# CH32M030C9U_PD-EVT.net
KiCad netlist of a schematic drawn in Altium Designer
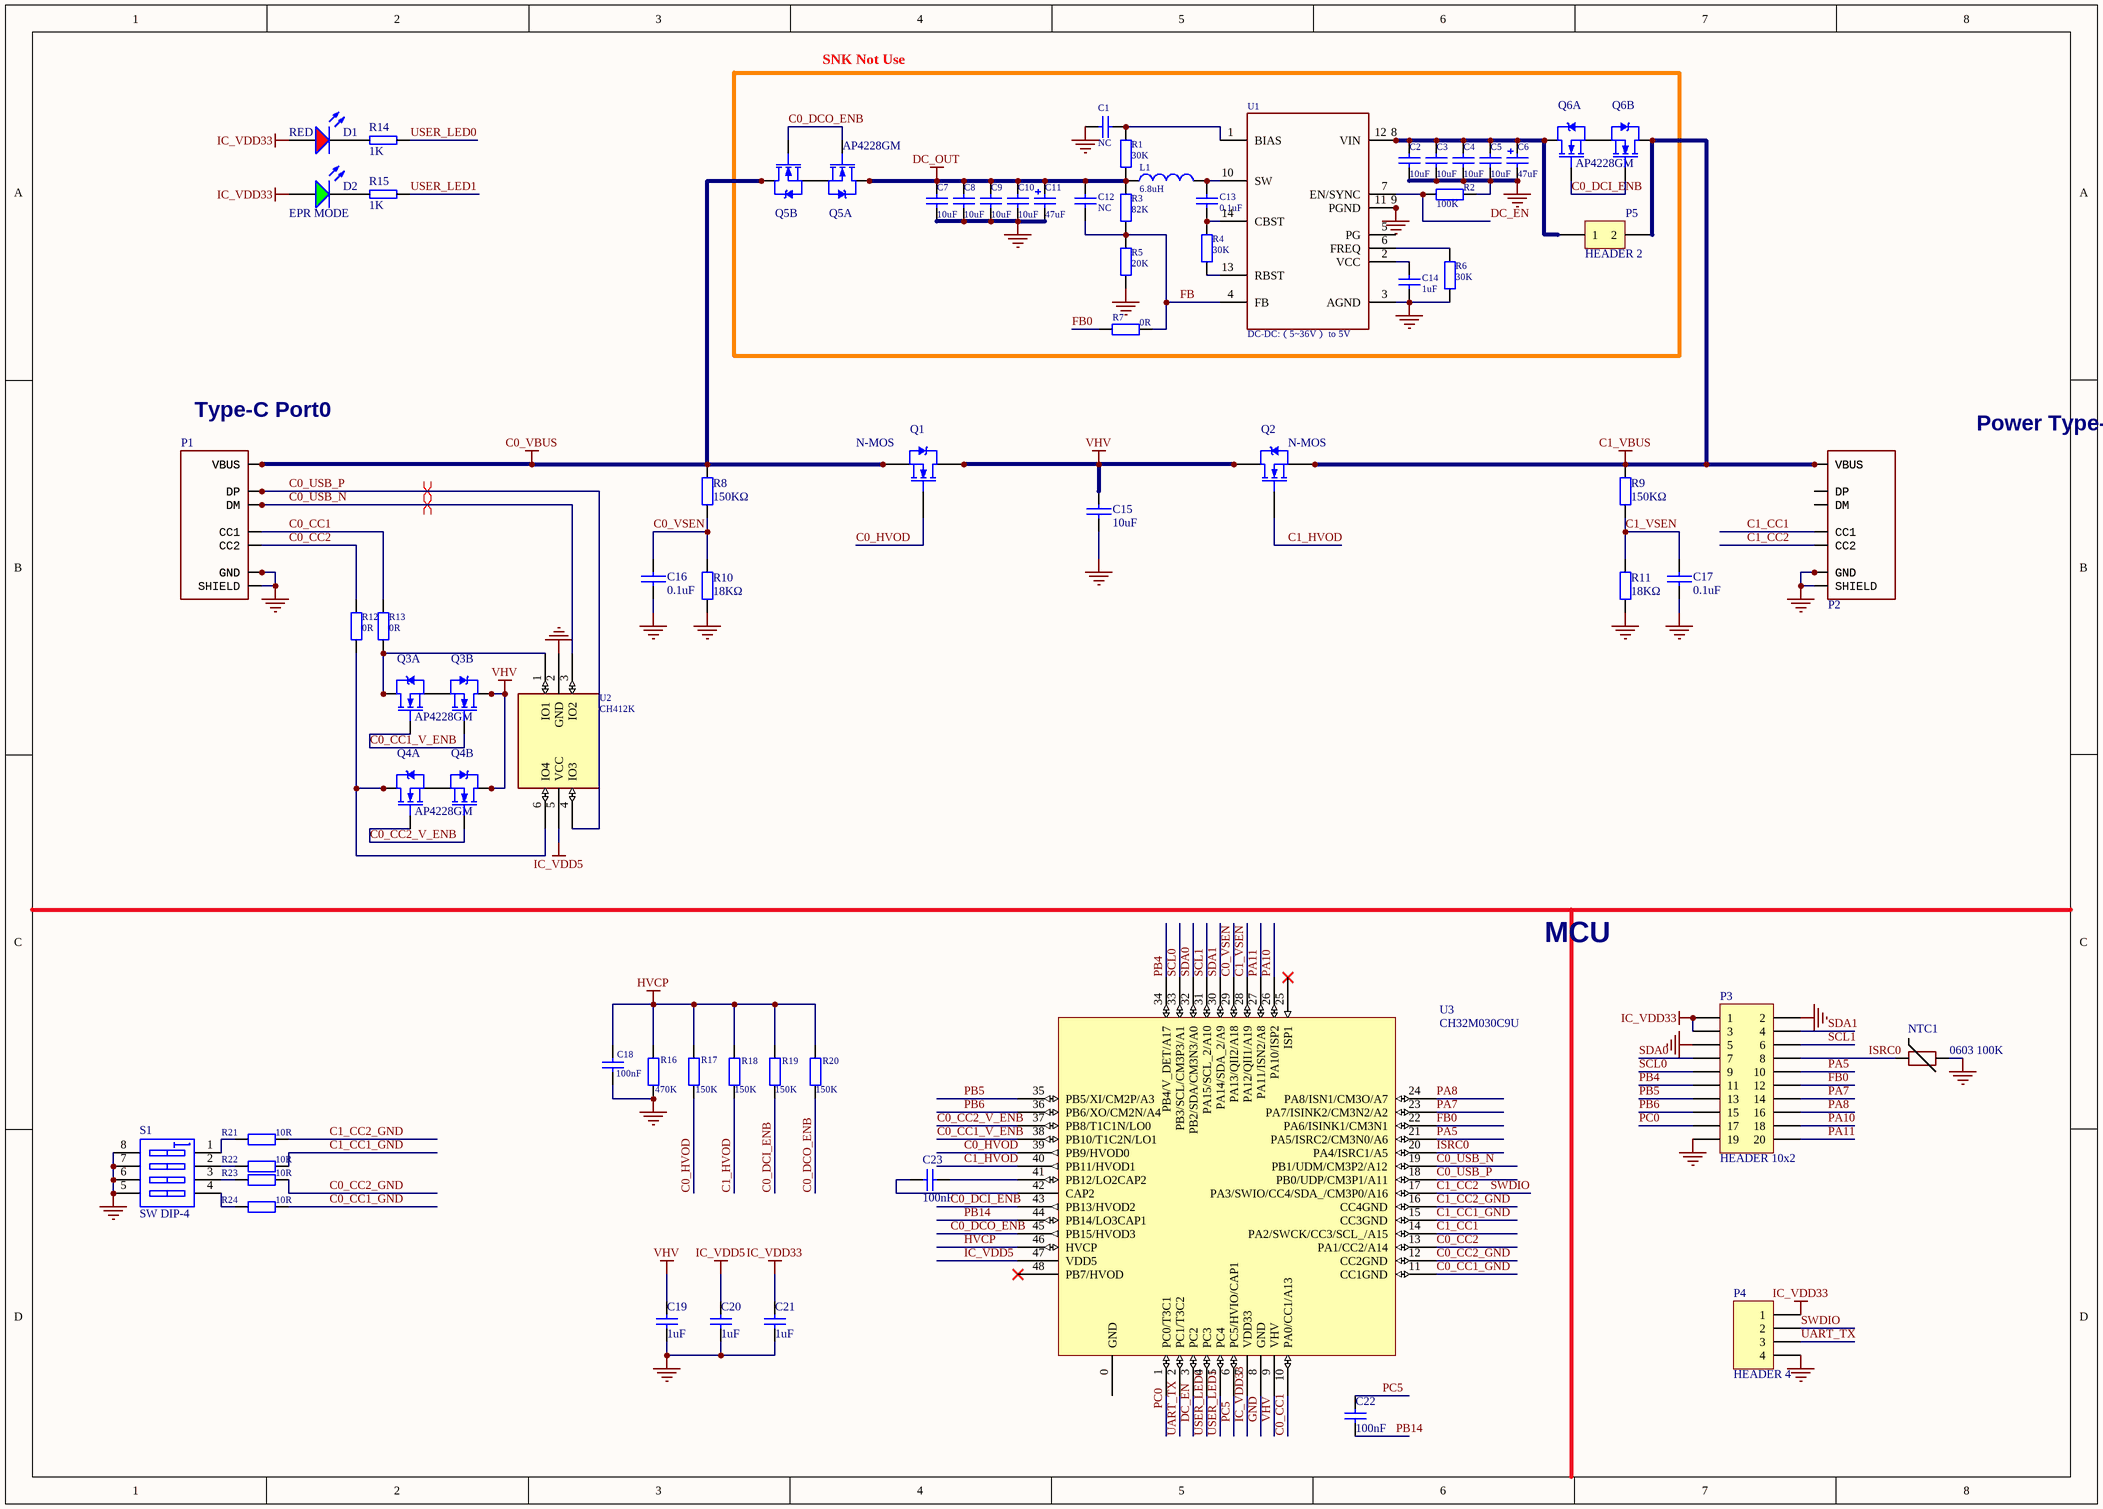
[diagram p0: CH32M030C9U_PD-EVT.SchDoc]

(export (version "E")
  (design (tool "Eeschema 10.0.6"))
  (components
    (comp (ref "C1")
      (value "NC")
      (footprint "0402_C")
      (description "贴片电容")
      (libsource (lib "Miscellaneous Devices LC") (part "0603 100nF (104) 10% 50V"))
    )
    (comp (ref "C2")
      (value "10uF")
      (footprint "0603_C")
      (description "贴片电容")
      (libsource (lib "Miscellaneous Devices LC") (part "0603 100nF (104) 10% 50V"))
    )
    (comp (ref "C3")
      (value "10uF")
      (footprint "0603_C")
      (description "贴片电容")
      (libsource (lib "Miscellaneous Devices LC") (part "0603 100nF (104) 10% 50V"))
    )
    (comp (ref "C4")
      (value "10uF")
      (footprint "0603_C")
      (description "贴片电容")
      (libsource (lib "Miscellaneous Devices LC") (part "0603 100nF (104) 10% 50V"))
    )
    (comp (ref "C5")
      (value "10uF")
      (footprint "0603_C")
      (description "贴片电容")
      (libsource (lib "Miscellaneous Devices LC") (part "0603 100nF (104) 10% 50V"))
    )
    (comp (ref "C6")
      (value "47uF")
      (footprint "1206_C")
      (description "钽电容")
      (libsource (lib "Miscellaneous Devices LC") (part "3216 10uF (106) 10% 16V"))
    )
    (comp (ref "C7")
      (value "10uF")
      (footprint "0603_C")
      (description "贴片电容")
      (libsource (lib "Miscellaneous Devices LC") (part "0603 100nF (104) 10% 50V"))
    )
    (comp (ref "C8")
      (value "10uF")
      (footprint "0603_C")
      (description "贴片电容")
      (libsource (lib "Miscellaneous Devices LC") (part "0603 100nF (104) 10% 50V"))
    )
    (comp (ref "C9")
      (value "10uF")
      (footprint "0603_C")
      (description "贴片电容")
      (libsource (lib "Miscellaneous Devices LC") (part "0603 100nF (104) 10% 50V"))
    )
    (comp (ref "C10")
      (value "10uF")
      (footprint "0603_C")
      (description "贴片电容")
      (libsource (lib "Miscellaneous Devices LC") (part "0603 100nF (104) 10% 50V"))
    )
    (comp (ref "C11")
      (value "47uF")
      (footprint "1206_C")
      (description "钽电容")
      (libsource (lib "Miscellaneous Devices LC") (part "3216 10uF (106) 10% 16V"))
    )
    (comp (ref "C12")
      (value "NC")
      (footprint "0402_C")
      (description "贴片电容")
      (libsource (lib "Miscellaneous Devices LC") (part "0603 100nF (104) 10% 50V"))
    )
    (comp (ref "C13")
      (value "0.1uF")
      (footprint "0402_C")
      (description "贴片电容")
      (libsource (lib "Miscellaneous Devices LC") (part "0603 100nF (104) 10% 50V"))
    )
    (comp (ref "C14")
      (value "1uF")
      (footprint "0402_C")
      (description "贴片电容")
      (libsource (lib "Miscellaneous Devices LC") (part "0603 100nF (104) 10% 50V"))
    )
    (comp (ref "C15")
      (value "10uF")
      (footprint "0603_C")
      (description "Capacitor")
      (libsource (lib "wch_sch_others") (part "CAP"))
    )
    (comp (ref "C16")
      (value "0.1uF")
      (footprint "0402_C")
      (description "Capacitor")
      (libsource (lib "wch_sch_others") (part "CAP"))
    )
    (comp (ref "C17")
      (value "0.1uF")
      (footprint "0402_C")
      (description "Capacitor")
      (libsource (lib "wch_sch_others") (part "CAP"))
    )
    (comp (ref "C18")
      (value "100nF")
      (footprint "0402_C")
      (description "贴片电容")
      (libsource (lib "Miscellaneous Devices LC") (part "0603 1uF (105) 10% 50V"))
    )
    (comp (ref "C19")
      (value "1uF")
      (footprint "0402_C")
      (description "贴片电容")
      (libsource (lib "Miscellaneous Devices LC") (part "0402 1.0uF (105) 10% 25V"))
    )
    (comp (ref "C20")
      (value "1uF")
      (footprint "0402_C")
      (description "贴片电容")
      (libsource (lib "Miscellaneous Devices LC") (part "0402 1.0uF (105) 10% 25V"))
    )
    (comp (ref "C21")
      (value "1uF")
      (footprint "0402_C")
      (description "贴片电容")
      (libsource (lib "Miscellaneous Devices LC") (part "0402 1.0uF (105) 10% 25V"))
    )
    (comp (ref "C22")
      (value "100nF")
      (footprint "0402_C")
      (description "贴片电容")
      (libsource (lib "Miscellaneous Devices LC") (part "0402 1.0uF (105) 10% 25V"))
    )
    (comp (ref "C23")
      (value "100nF")
      (footprint "0402_C")
      (description "贴片电容")
      (libsource (lib "Miscellaneous Devices LC") (part "0402 1.0uF (105) 10% 25V"))
    )
    (comp (ref "D1")
      (value "RED")
      (footprint "0603+")
      (description "发光二极管")
      (libsource (lib "wch_sch_others") (part "LED-RED"))
    )
    (comp (ref "D2")
      (value "EPR MODE")
      (footprint "0603+")
      (description "发光二极管")
      (libsource (lib "wch_sch_others") (part "LED-GREEN"))
    )
    (comp (ref "L1")
      (value "6.8uH")
      (footprint "IND-SMD_L11.5-W10.0")
      (description "C177243")
      (fields (field (name "PUBLISHER") "Altium Limited"))
      (libsource (lib "Miscellaneous Devices") (part "Inductor"))
    )
    (comp (ref "NTC1")
      (value "0603 100K")
      (footprint "0603")
      (libsource (lib "Miscellaneous SCH Lib") (part "NTC"))
    )
    (comp (ref "P1")
      (value "TYPE-C-Receptacle-RefDesign")
      (footprint "TYPE-C-Receptacle-2.0")
      (libsource (lib "") (part "TYPE-C-Receptacle-RefDesign_1"))
    )
    (comp (ref "P2")
      (value "TYPE-C-Receptacle-RefDesign")
      (footprint "TYPE-C-Receptacle-2.0")
      (libsource (lib "Miscellaneous SCH Lib") (part "TYPE-C-Receptacle-RefDesign"))
    )
    (comp (ref "P3")
      (value "HEADER 10x2")
      (footprint "MYPCB:IDC20-2.54MM")
      (description "Header, 10-Pin, Dual row")
      (libsource (lib "wch_sch_others") (part "HEADER 10x2"))
    )
    (comp (ref "P4")
      (value "HEADER 4")
      (footprint "SIP4-2.54mm")
      (description "Header, 4-Pin")
      (libsource (lib "wch_sch_others") (part "HEADER 4"))
    )
    (comp (ref "P5")
      (value "HEADER 2")
      (footprint "MYPCB:SIP2-2.54mm")
      (description "Header, 2-Pin")
      (libsource (lib "wch_sch_others") (part "HEADER 2_1"))
    )
    (comp (ref "Q1")
      (value "N-MOS")
      (footprint "DFN-8_L3.1-W3.0-P0.65-LS3.3-BL")
      (description "N-MOS 8p")
      (libsource (lib "Miscellaneous SCH Lib") (part "N-MOS"))
    )
    (comp (ref "Q2")
      (value "N-MOS")
      (footprint "DFN-8_L3.1-W3.0-P0.65-LS3.3-BL")
      (description "N-MOS 8p")
      (libsource (lib "Miscellaneous SCH Lib") (part "N-MOS"))
    )
    (comp (ref "Q3")
      (value "AP4228GM")
      (footprint "DFN-8_Dual_EP_3x3mm")
      (description "Dual N MOS")
      (libsource (lib "Miscellaneous SCH Lib") (part "AP4228GM"))
    )
    (comp (ref "Q4")
      (value "AP4228GM")
      (footprint "DFN-8_Dual_EP_3x3mm")
      (description "Dual N MOS")
      (libsource (lib "Miscellaneous SCH Lib") (part "AP4228GM"))
    )
    (comp (ref "Q5")
      (value "AP4228GM")
      (footprint "DFN-8_Dual_EP_3x3mm")
      (description "Dual N MOS")
      (libsource (lib "Miscellaneous SCH Lib") (part "AP4228GM"))
    )
    (comp (ref "Q6")
      (value "AP4228GM")
      (footprint "DFN-8_Dual_EP_3x3mm")
      (description "Dual N MOS")
      (libsource (lib "Miscellaneous SCH Lib") (part "AP4228GM"))
    )
    (comp (ref "R1")
      (value "30K")
      (footprint "0402")
      (description "贴片电阻")
      (libsource (lib "Miscellaneous Devices LC") (part "0603 470Ω (4700) 1%"))
    )
    (comp (ref "R2")
      (value "100K")
      (footprint "0402")
      (description "贴片电阻")
      (libsource (lib "") (part "0603 470Ω (4700) 1%_1"))
    )
    (comp (ref "R3")
      (value "82K")
      (footprint "0402")
      (description "贴片电阻")
      (libsource (lib "Miscellaneous Devices LC") (part "0603 470Ω (4700) 1%"))
    )
    (comp (ref "R4")
      (value "30K")
      (footprint "0402")
      (description "贴片电阻")
      (libsource (lib "Miscellaneous Devices LC") (part "0603 470Ω (4700) 1%"))
    )
    (comp (ref "R5")
      (value "20K")
      (footprint "0402")
      (description "贴片电阻")
      (libsource (lib "Miscellaneous Devices LC") (part "0603 470Ω (4700) 1%"))
    )
    (comp (ref "R6")
      (value "30K")
      (footprint "0402")
      (description "贴片电阻")
      (libsource (lib "Miscellaneous Devices LC") (part "0603 470Ω (4700) 1%"))
    )
    (comp (ref "R7")
      (value "0R")
      (footprint "0402")
      (description "贴片电阻")
      (libsource (lib "") (part "0603 100KΩ (1003) 1%_3"))
    )
    (comp (ref "R8")
      (value "150KΩ")
      (footprint "0402")
      (description "贴片电阻")
      (libsource (lib "Miscellaneous Devices LC") (part "0603 56KΩ (5602) 1%"))
    )
    (comp (ref "R9")
      (value "150KΩ")
      (footprint "0402")
      (description "贴片电阻")
      (libsource (lib "Miscellaneous Devices LC") (part "0603 56KΩ (5602) 1%"))
    )
    (comp (ref "R10")
      (value "18KΩ")
      (footprint "0402")
      (description "贴片电阻")
      (libsource (lib "Miscellaneous Devices LC") (part "0603 56KΩ (5602) 1%"))
    )
    (comp (ref "R11")
      (value "18KΩ")
      (footprint "0402")
      (description "贴片电阻")
      (libsource (lib "Miscellaneous Devices LC") (part "0603 56KΩ (5602) 1%"))
    )
    (comp (ref "R12")
      (value "0R")
      (footprint "0402")
      (description "贴片电阻")
      (libsource (lib "") (part "0603 100KΩ (1003) 1%_1"))
    )
    (comp (ref "R13")
      (value "0R")
      (footprint "0402")
      (description "贴片电阻")
      (libsource (lib "") (part "0603 100KΩ (1003) 1%_1"))
    )
    (comp (ref "R14") (value "1K") (footprint "0402") (libsource (lib "wch_sch_others") (part "RES")))
    (comp (ref "R15") (value "1K") (footprint "0402") (libsource (lib "wch_sch_others") (part "RES")))
    (comp (ref "R16")
      (value "470K")
      (footprint "0402")
      (description "贴片电阻")
      (libsource (lib "Miscellaneous Devices LC") (part "0603 100KΩ (1003) 1%"))
    )
    (comp (ref "R17")
      (value "150K")
      (footprint "0402")
      (description "贴片电阻")
      (libsource (lib "Miscellaneous Devices LC") (part "0603 100KΩ (1003) 1%"))
    )
    (comp (ref "R18")
      (value "150K")
      (footprint "0402")
      (description "贴片电阻")
      (libsource (lib "Miscellaneous Devices LC") (part "0603 100KΩ (1003) 1%"))
    )
    (comp (ref "R19")
      (value "150K")
      (footprint "0402")
      (description "贴片电阻")
      (libsource (lib "Miscellaneous Devices LC") (part "0603 100KΩ (1003) 1%"))
    )
    (comp (ref "R20")
      (value "150K")
      (footprint "0402")
      (description "贴片电阻")
      (libsource (lib "Miscellaneous Devices LC") (part "0603 100KΩ (1003) 1%"))
    )
    (comp (ref "R21")
      (value "10R")
      (footprint "0402")
      (description "贴片电阻")
      (libsource (lib "") (part "0603 100KΩ (1003) 1%_2"))
    )
    (comp (ref "R22")
      (value "10R")
      (footprint "0402")
      (description "贴片电阻")
      (libsource (lib "") (part "0603 100KΩ (1003) 1%_2"))
    )
    (comp (ref "R23")
      (value "10R")
      (footprint "0402")
      (description "贴片电阻")
      (libsource (lib "") (part "0603 100KΩ (1003) 1%_2"))
    )
    (comp (ref "R24")
      (value "10R")
      (footprint "0402")
      (description "贴片电阻")
      (libsource (lib "") (part "0603 100KΩ (1003) 1%_2"))
    )
    (comp (ref "S1")
      (value "SW DIP-4")
      (footprint "SW-TH_8P-P2.54-LS7.62")
      (description "DIP Switch, 4 Position, SPST")
      (libsource (lib "wch_sch_others") (part "SW DIP-4"))
    )
    (comp (ref "U1")
      (value "DC-DC:（5~36V） to 5V")
      (footprint "EVQFN14_4X3.5")
      (libsource (lib "PCB_Project") (part "DC-DC"))
    )
    (comp (ref "U2")
      (value "CH412K")
      (footprint "SOT-363")
      (description "Qaud ESD protect, high speed")
      (libsource (lib "CHXXX") (part "CH412K"))
    )
    (comp (ref "U3")
      (value "CH32M030C9U")
      (footprint "QFN48_5X5")
      (description "RISC-V MCU, 72MHz, USB, Type-C/PD, OPA, CMP, 28V LDO & HVIO")
      (libsource (lib "CH32M030C9U_PD-EVT") (part "CH32M030C9U"))
    )
  )
  (nets
    (net (code "1") (name "/C0_CC1") (class "Default")
      (node (ref "P1") (pin "A5") (pinfunction "CC1_A5") (pintype "passive"))
      (node (ref "R13") (pin "1") (pinfunction "1_1") (pintype "passive"))
      (node (ref "U3") (pin "10") (pinfunction "PA0/CC1/A13_10") (pintype "bidirectional"))
    )
    (net (code "2") (name "/C0_CC1_GND") (class "Default")
      (node (ref "R24") (pin "1") (pinfunction "1_1") (pintype "passive"))
      (node (ref "U3") (pin "11") (pinfunction "CC1GND_11") (pintype "bidirectional"))
    )
    (net (code "3") (name "/C0_CC1_V_ENB") (class "Default")
      (node (ref "Q3") (pin "2") (pinfunction "G1_2") (pintype "passive"))
      (node (ref "Q3") (pin "4") (pinfunction "G2_4") (pintype "passive"))
      (node (ref "U3") (pin "38") (pinfunction "PB10/T1C2N/LO1_38") (pintype "bidirectional"))
    )
    (net (code "4") (name "/C0_CC2") (class "Default")
      (node (ref "P1") (pin "B5") (pinfunction "CC2_B5") (pintype "passive"))
      (node (ref "R12") (pin "1") (pinfunction "1_1") (pintype "passive"))
      (node (ref "U3") (pin "13") (pinfunction "PA1/CC2/A14_13") (pintype "bidirectional"))
    )
    (net (code "5") (name "/C0_CC2_GND") (class "Default")
      (node (ref "R23") (pin "1") (pinfunction "1_1") (pintype "passive"))
      (node (ref "U3") (pin "12") (pinfunction "CC2GND_12") (pintype "bidirectional"))
    )
    (net (code "6") (name "/C0_CC2_V_ENB") (class "Default")
      (node (ref "Q4") (pin "2") (pinfunction "G1_2") (pintype "passive"))
      (node (ref "Q4") (pin "4") (pinfunction "G2_4") (pintype "passive"))
      (node (ref "U3") (pin "37") (pinfunction "PB8/T1C1N/LO0_37") (pintype "bidirectional"))
    )
    (net (code "7") (name "/C0_DCI_ENB") (class "Default")
      (node (ref "Q6") (pin "2") (pinfunction "G1_2") (pintype "passive"))
      (node (ref "Q6") (pin "4") (pinfunction "G2_4") (pintype "passive"))
      (node (ref "R19") (pin "1") (pinfunction "1_1") (pintype "passive"))
      (node (ref "U3") (pin "43") (pinfunction "PB13/HVOD2_43") (pintype "output"))
    )
    (net (code "8") (name "/C0_DCO_ENB") (class "Default")
      (node (ref "Q5") (pin "2") (pinfunction "G1_2") (pintype "passive"))
      (node (ref "Q5") (pin "4") (pinfunction "G2_4") (pintype "passive"))
      (node (ref "R20") (pin "1") (pinfunction "1_1") (pintype "passive"))
      (node (ref "U3") (pin "45") (pinfunction "PB15/HVOD3_45") (pintype "output"))
    )
    (net (code "9") (name "/C0_HVOD") (class "Default")
      (node (ref "Q1") (pin "4") (pinfunction "G_4") (pintype "passive"))
      (node (ref "R17") (pin "1") (pinfunction "1_1") (pintype "passive"))
      (node (ref "U3") (pin "39") (pinfunction "PB9/HVOD0_39") (pintype "output"))
    )
    (net (code "10") (name "/C0_USB_N") (class "Default")
      (node (ref "P1") (pin "A7") (pinfunction "DM_A7") (pintype "passive"))
      (node (ref "P1") (pin "B7") (pinfunction "DM_B7") (pintype "passive"))
      (node (ref "U2") (pin "3") (pinfunction "IO2_3") (pintype "bidirectional"))
      (node (ref "U3") (pin "19") (pinfunction "PB1/UDM/CM3P2/A12_19") (pintype "bidirectional"))
    )
    (net (code "11") (name "/C0_USB_P") (class "Default")
      (node (ref "P1") (pin "A6") (pinfunction "DP_A6") (pintype "passive"))
      (node (ref "P1") (pin "B6") (pinfunction "DP_B6") (pintype "passive"))
      (node (ref "U2") (pin "4") (pinfunction "IO3_4") (pintype "bidirectional"))
      (node (ref "U3") (pin "18") (pinfunction "PB0/UDP/CM3P1/A11_18") (pintype "bidirectional"))
    )
    (net (code "12") (name "/C0_VSEN") (class "Default")
      (node (ref "C16") (pin "2") (pinfunction "2_2") (pintype "passive"))
      (node (ref "R10") (pin "1") (pinfunction "1_1") (pintype "passive"))
      (node (ref "R8") (pin "2") (pinfunction "2_2") (pintype "passive"))
      (node (ref "U3") (pin "29") (pinfunction "PA13/QII2/A18_29") (pintype "bidirectional"))
    )
    (net (code "13") (name "/C1_CC1") (class "Default")
      (node (ref "P2") (pin "A5") (pinfunction "CC1_A5") (pintype "passive"))
      (node (ref "U3") (pin "14") (pinfunction "PA2/SWCK/CC3/SCL_/A15_14") (pintype "bidirectional"))
    )
    (net (code "14") (name "/C1_CC1_GND") (class "Default")
      (node (ref "R22") (pin "1") (pinfunction "1_1") (pintype "passive"))
      (node (ref "U3") (pin "15") (pinfunction "CC3GND_15") (pintype "bidirectional"))
    )
    (net (code "15") (name "/C1_CC2") (class "Default")
      (node (ref "P2") (pin "B5") (pinfunction "CC2_B5") (pintype "passive"))
      (node (ref "P4") (pin "2") (pinfunction "2_2") (pintype "passive"))
      (node (ref "U3") (pin "17") (pinfunction "PA3/SWIO/CC4/SDA_/CM3P0/A16_17") (pintype "bidirectional"))
    )
    (net (code "16") (name "/C1_CC2_GND") (class "Default")
      (node (ref "R21") (pin "1") (pinfunction "1_1") (pintype "passive"))
      (node (ref "U3") (pin "16") (pinfunction "CC4GND_16") (pintype "bidirectional"))
    )
    (net (code "17") (name "/C1_HVOD") (class "Default")
      (node (ref "Q2") (pin "4") (pinfunction "G_4") (pintype "passive"))
      (node (ref "R18") (pin "1") (pinfunction "1_1") (pintype "passive"))
      (node (ref "U3") (pin "40") (pinfunction "PB11/HVOD1_40") (pintype "output"))
    )
    (net (code "18") (name "/C1_VSEN") (class "Default")
      (node (ref "C17") (pin "2") (pinfunction "2_2") (pintype "passive"))
      (node (ref "R11") (pin "1") (pinfunction "1_1") (pintype "passive"))
      (node (ref "R9") (pin "2") (pinfunction "2_2") (pintype "passive"))
      (node (ref "U3") (pin "28") (pinfunction "PA12/QII1/A19_28") (pintype "bidirectional"))
    )
    (net (code "19") (name "/DC_EN") (class "Default")
      (node (ref "R2") (pin "1") (pinfunction "1_1") (pintype "passive"))
      (node (ref "U1") (pin "7") (pinfunction "EN/SYNC_7") (pintype "passive"))
      (node (ref "U3") (pin "3") (pinfunction "PC2_3") (pintype "bidirectional"))
    )
    (net (code "20") (name "/FB") (class "Default")
      (node (ref "C12") (pin "1") (pinfunction "1_1") (pintype "passive"))
      (node (ref "R3") (pin "2") (pinfunction "2_2") (pintype "passive"))
      (node (ref "R5") (pin "1") (pinfunction "1_1") (pintype "passive"))
      (node (ref "R7") (pin "2") (pinfunction "2_2") (pintype "passive"))
      (node (ref "U1") (pin "4") (pinfunction "FB_4") (pintype "passive"))
    )
    (net (code "21") (name "/FB0") (class "Default")
      (node (ref "P3") (pin "12") (pinfunction "12_12") (pintype "passive"))
      (node (ref "R7") (pin "1") (pinfunction "1_1") (pintype "passive"))
      (node (ref "U3") (pin "22") (pinfunction "PA6/ISINK1/CM3N1_22") (pintype "bidirectional"))
    )
    (net (code "22") (name "/ISRC0") (class "Default")
      (node (ref "NTC1") (pin "1") (pintype "passive"))
      (node (ref "P3") (pin "8") (pinfunction "8_8") (pintype "passive"))
      (node (ref "U3") (pin "20") (pinfunction "PA4/ISRC1/A5_20") (pintype "bidirectional"))
    )
    (net (code "23") (name "/PA5") (class "Default")
      (node (ref "P3") (pin "10") (pinfunction "10_10") (pintype "passive"))
      (node (ref "U3") (pin "21") (pinfunction "PA5/ISRC2/CM3N0/A6_21") (pintype "bidirectional"))
    )
    (net (code "24") (name "/PA7") (class "Default")
      (node (ref "P3") (pin "14") (pinfunction "14_14") (pintype "passive"))
      (node (ref "U3") (pin "23") (pinfunction "PA7/ISINK2/CM3N2/A2_23") (pintype "bidirectional"))
    )
    (net (code "25") (name "/PA8") (class "Default")
      (node (ref "P3") (pin "16") (pinfunction "16_16") (pintype "passive"))
      (node (ref "U3") (pin "24") (pinfunction "PA8/ISN1/CM3O/A7_24") (pintype "bidirectional"))
    )
    (net (code "26") (name "/PA10") (class "Default")
      (node (ref "P3") (pin "18") (pinfunction "18_18") (pintype "passive"))
      (node (ref "U3") (pin "26") (pinfunction "PA10/ISP2_26") (pintype "bidirectional"))
    )
    (net (code "27") (name "/PA11") (class "Default")
      (node (ref "P3") (pin "20") (pinfunction "20_20") (pintype "passive"))
      (node (ref "U3") (pin "27") (pinfunction "PA11/ISN2/A8_27") (pintype "bidirectional"))
    )
    (net (code "28") (name "/PB4") (class "Default")
      (node (ref "P3") (pin "11") (pinfunction "11_11") (pintype "passive"))
      (node (ref "U3") (pin "34") (pinfunction "PB4/V_DET/A17_34") (pintype "bidirectional"))
    )
    (net (code "29") (name "/PB5") (class "Default")
      (node (ref "P3") (pin "13") (pinfunction "13_13") (pintype "passive"))
      (node (ref "U3") (pin "35") (pinfunction "PB5/XI/CM2P/A3_35") (pintype "bidirectional"))
    )
    (net (code "30") (name "/PB6") (class "Default")
      (node (ref "P3") (pin "15") (pinfunction "15_15") (pintype "passive"))
      (node (ref "U3") (pin "36") (pinfunction "PB6/XO/CM2N/A4_36") (pintype "bidirectional"))
    )
    (net (code "31") (name "/PB14") (class "Default")
      (node (ref "C22") (pin "1") (pinfunction "1_1") (pintype "passive"))
      (node (ref "U3") (pin "44") (pinfunction "PB14/LO3CAP1_44") (pintype "bidirectional"))
    )
    (net (code "32") (name "/PC0") (class "Default")
      (node (ref "P3") (pin "17") (pinfunction "17_17") (pintype "passive"))
      (node (ref "U3") (pin "1") (pinfunction "PC0/T3C1_1") (pintype "bidirectional"))
    )
    (net (code "33") (name "/PC5") (class "Default")
      (node (ref "C22") (pin "2") (pinfunction "2_2") (pintype "passive"))
      (node (ref "U3") (pin "6") (pinfunction "PC5/HVIO/CAP1_6") (pintype "bidirectional"))
    )
    (net (code "34") (name "/SCL0") (class "Default")
      (node (ref "P3") (pin "9") (pinfunction "9_9") (pintype "passive"))
      (node (ref "U3") (pin "33") (pinfunction "PB3/SCL/CM3P3/A1_33") (pintype "bidirectional"))
    )
    (net (code "35") (name "/SCL1") (class "Default")
      (node (ref "P3") (pin "6") (pinfunction "6_6") (pintype "passive"))
      (node (ref "U3") (pin "31") (pinfunction "PA15/SCL_2/A10_31") (pintype "bidirectional"))
    )
    (net (code "36") (name "/SDA0") (class "Default")
      (node (ref "P3") (pin "7") (pinfunction "7_7") (pintype "passive"))
      (node (ref "U3") (pin "32") (pinfunction "PB2/SDA/CM3N3/A0_32") (pintype "bidirectional"))
    )
    (net (code "37") (name "/SDA1") (class "Default")
      (node (ref "P3") (pin "4") (pinfunction "4_4") (pintype "passive"))
      (node (ref "U3") (pin "30") (pinfunction "PA14/SDA_2/A9_30") (pintype "bidirectional"))
    )
    (net (code "38") (name "/UART_TX") (class "Default")
      (node (ref "P4") (pin "3") (pinfunction "3_3") (pintype "passive"))
      (node (ref "U3") (pin "2") (pinfunction "PC1/T3C2_2") (pintype "bidirectional"))
    )
    (net (code "39") (name "/USER_LED0") (class "Default")
      (node (ref "R14") (pin "2") (pintype "passive"))
      (node (ref "U3") (pin "4") (pinfunction "PC3_4") (pintype "bidirectional"))
    )
    (net (code "40") (name "/USER_LED1") (class "Default")
      (node (ref "R15") (pin "2") (pintype "passive"))
      (node (ref "U3") (pin "5") (pinfunction "PC4_5") (pintype "bidirectional"))
    )
    (net (code "41") (name "C0_VBUS") (class "Default")
      (node (ref "P1") (pin "A4") (pinfunction "VBUS_A4") (pintype "passive"))
      (node (ref "P1") (pin "A9") (pinfunction "VBUS_A9") (pintype "passive"))
      (node (ref "P1") (pin "B4") (pinfunction "VBUS_B4") (pintype "passive"))
      (node (ref "P1") (pin "B9") (pinfunction "VBUS_B9") (pintype "passive"))
      (node (ref "Q1") (pin "1") (pinfunction "S_1") (pintype "passive"))
      (node (ref "Q1") (pin "2") (pinfunction "2_2") (pintype "passive"))
      (node (ref "Q1") (pin "3") (pinfunction "3_3") (pintype "passive"))
      (node (ref "Q5") (pin "5") (pinfunction "D2_5") (pintype "passive"))
      (node (ref "Q5") (pin "6") (pinfunction "D2_6") (pintype "passive"))
      (node (ref "R8") (pin "1") (pinfunction "1_1") (pintype "passive"))
    )
    (net (code "42") (name "C1_VBUS") (class "Default")
      (node (ref "P2") (pin "A4") (pinfunction "VBUS_A4") (pintype "passive"))
      (node (ref "P2") (pin "A9") (pinfunction "VBUS_A9") (pintype "passive"))
      (node (ref "P2") (pin "B4") (pinfunction "VBUS_B4") (pintype "passive"))
      (node (ref "P2") (pin "B9") (pinfunction "VBUS_B9") (pintype "passive"))
      (node (ref "P5") (pin "2") (pinfunction "2_2") (pintype "passive"))
      (node (ref "Q2") (pin "1") (pinfunction "S_1") (pintype "passive"))
      (node (ref "Q2") (pin "2") (pinfunction "2_2") (pintype "passive"))
      (node (ref "Q2") (pin "3") (pinfunction "3_3") (pintype "passive"))
      (node (ref "Q6") (pin "5") (pinfunction "D2_5") (pintype "passive"))
      (node (ref "Q6") (pin "6") (pinfunction "D2_6") (pintype "passive"))
      (node (ref "R9") (pin "1") (pinfunction "1_1") (pintype "passive"))
    )
    (net (code "43") (name "DC_OUT") (class "Default")
      (node (ref "C10") (pin "2") (pinfunction "2_2") (pintype "passive"))
      (node (ref "C11") (pin "1") (pinfunction "1_1") (pintype "passive"))
      (node (ref "C12") (pin "2") (pinfunction "2_2") (pintype "passive"))
      (node (ref "C7") (pin "2") (pinfunction "2_2") (pintype "passive"))
      (node (ref "C8") (pin "2") (pinfunction "2_2") (pintype "passive"))
      (node (ref "C9") (pin "2") (pinfunction "2_2") (pintype "passive"))
      (node (ref "L1") (pin "2") (pinfunction "2_2") (pintype "passive"))
      (node (ref "Q5") (pin "7") (pinfunction "D1_7") (pintype "passive"))
      (node (ref "Q5") (pin "8") (pinfunction "D1_8") (pintype "passive"))
      (node (ref "R1") (pin "2") (pinfunction "2_2") (pintype "passive"))
      (node (ref "R3") (pin "1") (pinfunction "1_1") (pintype "passive"))
    )
    (net (code "44") (name "GND") (class "Default")
      (node (ref "C1") (pin "2") (pinfunction "2_2") (pintype "passive"))
      (node (ref "C10") (pin "1") (pinfunction "1_1") (pintype "passive"))
      (node (ref "C11") (pin "2") (pinfunction "2_2") (pintype "passive"))
      (node (ref "C14") (pin "2") (pinfunction "2_2") (pintype "passive"))
      (node (ref "C15") (pin "1") (pinfunction "1_1") (pintype "passive"))
      (node (ref "C16") (pin "1") (pinfunction "1_1") (pintype "passive"))
      (node (ref "C17") (pin "1") (pinfunction "1_1") (pintype "passive"))
      (node (ref "C18") (pin "2") (pinfunction "2_2") (pintype "passive"))
      (node (ref "C19") (pin "2") (pinfunction "2_2") (pintype "passive"))
      (node (ref "C2") (pin "1") (pinfunction "1_1") (pintype "passive"))
      (node (ref "C20") (pin "2") (pinfunction "2_2") (pintype "passive"))
      (node (ref "C21") (pin "2") (pinfunction "2_2") (pintype "passive"))
      (node (ref "C3") (pin "1") (pinfunction "1_1") (pintype "passive"))
      (node (ref "C4") (pin "1") (pinfunction "1_1") (pintype "passive"))
      (node (ref "C5") (pin "1") (pinfunction "1_1") (pintype "passive"))
      (node (ref "C6") (pin "2") (pinfunction "2_2") (pintype "passive"))
      (node (ref "C7") (pin "1") (pinfunction "1_1") (pintype "passive"))
      (node (ref "C8") (pin "1") (pinfunction "1_1") (pintype "passive"))
      (node (ref "C9") (pin "1") (pinfunction "1_1") (pintype "passive"))
      (node (ref "NTC1") (pin "2") (pintype "passive"))
      (node (ref "P1") (pin "0") (pinfunction "SHIELD_0") (pintype "passive"))
      (node (ref "P1") (pin "A1") (pinfunction "GND_A1") (pintype "passive"))
      (node (ref "P1") (pin "A12") (pinfunction "GND_A12") (pintype "passive"))
      (node (ref "P1") (pin "B1") (pinfunction "GND_B1") (pintype "passive"))
      (node (ref "P1") (pin "B12") (pinfunction "GND_B12") (pintype "passive"))
      (node (ref "P2") (pin "0") (pinfunction "SHIELD_0") (pintype "passive"))
      (node (ref "P2") (pin "A1") (pinfunction "GND_A1") (pintype "passive"))
      (node (ref "P2") (pin "A12") (pinfunction "GND_A12") (pintype "passive"))
      (node (ref "P2") (pin "B1") (pinfunction "GND_B1") (pintype "passive"))
      (node (ref "P2") (pin "B12") (pinfunction "GND_B12") (pintype "passive"))
      (node (ref "P3") (pin "19") (pinfunction "19_19") (pintype "passive"))
      (node (ref "P3") (pin "2") (pinfunction "2_2") (pintype "passive"))
      (node (ref "P3") (pin "5") (pinfunction "5_5") (pintype "passive"))
      (node (ref "P4") (pin "4") (pinfunction "4_4") (pintype "passive"))
      (node (ref "R10") (pin "2") (pinfunction "2_2") (pintype "passive"))
      (node (ref "R11") (pin "2") (pinfunction "2_2") (pintype "passive"))
      (node (ref "R16") (pin "1") (pinfunction "1_1") (pintype "passive"))
      (node (ref "R2") (pin "2") (pinfunction "2_2") (pintype "passive"))
      (node (ref "R5") (pin "2") (pinfunction "2_2") (pintype "passive"))
      (node (ref "R6") (pin "2") (pinfunction "2_2") (pintype "passive"))
      (node (ref "S1") (pin "5") (pinfunction "5_5") (pintype "passive"))
      (node (ref "S1") (pin "6") (pinfunction "6_6") (pintype "passive"))
      (node (ref "S1") (pin "7") (pinfunction "7_7") (pintype "passive"))
      (node (ref "S1") (pin "8") (pinfunction "8_8") (pintype "passive"))
      (node (ref "U1") (pin "11") (pinfunction "PGND_11") (pintype "passive"))
      (node (ref "U1") (pin "3") (pinfunction "AGND_3") (pintype "passive"))
      (node (ref "U1") (pin "9") (pinfunction "PGND_9") (pintype "passive"))
      (node (ref "U2") (pin "2") (pinfunction "GND_2") (pintype "power_in"))
      (node (ref "U3") (pin "8") (pinfunction "GND_8") (pintype "power_in"))
    )
    (net (code "45") (name "HVCP") (class "Default")
      (node (ref "C18") (pin "1") (pinfunction "1_1") (pintype "passive"))
      (node (ref "R16") (pin "2") (pinfunction "2_2") (pintype "passive"))
      (node (ref "R17") (pin "2") (pinfunction "2_2") (pintype "passive"))
      (node (ref "R18") (pin "2") (pinfunction "2_2") (pintype "passive"))
      (node (ref "R19") (pin "2") (pinfunction "2_2") (pintype "passive"))
      (node (ref "R20") (pin "2") (pinfunction "2_2") (pintype "passive"))
      (node (ref "U3") (pin "46") (pinfunction "HVCP_46") (pintype "bidirectional"))
    )
    (net (code "46") (name "IC_VDD5") (class "Default")
      (node (ref "C20") (pin "1") (pinfunction "1_1") (pintype "passive"))
      (node (ref "U2") (pin "5") (pinfunction "VCC_5") (pintype "power_in"))
      (node (ref "U3") (pin "47") (pinfunction "VDD5_47") (pintype "power_in"))
    )
    (net (code "47") (name "IC_VDD33") (class "Default")
      (node (ref "C21") (pin "1") (pinfunction "1_1") (pintype "passive"))
      (node (ref "D1") (pin "1") (pinfunction "A_1") (pintype "passive"))
      (node (ref "D2") (pin "1") (pinfunction "A_1") (pintype "passive"))
      (node (ref "P3") (pin "1") (pinfunction "1_1") (pintype "passive"))
      (node (ref "P3") (pin "3") (pinfunction "3_3") (pintype "passive"))
      (node (ref "P4") (pin "1") (pinfunction "1_1") (pintype "passive"))
      (node (ref "U3") (pin "7") (pinfunction "VDD33_7") (pintype "power_in"))
    )
    (net (code "48") (name "Net-(C2-Pad2)") (class "Default")
      (node (ref "C2") (pin "2") (pinfunction "2_2") (pintype "passive"))
      (node (ref "C3") (pin "2") (pinfunction "2_2") (pintype "passive"))
      (node (ref "C4") (pin "2") (pinfunction "2_2") (pintype "passive"))
      (node (ref "C5") (pin "2") (pinfunction "2_2") (pintype "passive"))
      (node (ref "C6") (pin "1") (pinfunction "1_1") (pintype "passive"))
      (node (ref "P5") (pin "1") (pinfunction "1_1") (pintype "passive"))
      (node (ref "Q6") (pin "7") (pinfunction "D1_7") (pintype "passive"))
      (node (ref "Q6") (pin "8") (pinfunction "D1_8") (pintype "passive"))
      (node (ref "U1") (pin "12") (pinfunction "VIN_12") (pintype "passive"))
      (node (ref "U1") (pin "8") (pinfunction "VIN_8") (pintype "passive"))
    )
    (net (code "49") (name "Net-(D1-K)") (class "Default")
      (node (ref "D1") (pin "2") (pinfunction "K_2") (pintype "passive"))
      (node (ref "R14") (pin "1") (pintype "passive"))
    )
    (net (code "50") (name "Net-(D2-K)") (class "Default")
      (node (ref "D2") (pin "2") (pinfunction "K_2") (pintype "passive"))
      (node (ref "R15") (pin "1") (pintype "passive"))
    )
    (net (code "51") (name "Net-(P2-DM-PadA7)") (class "Default")
      (node (ref "P2") (pin "A7") (pinfunction "DM_A7") (pintype "passive"))
      (node (ref "P2") (pin "B7") (pinfunction "DM_B7") (pintype "passive"))
    )
    (net (code "52") (name "Net-(P2-DP-PadA6)") (class "Default")
      (node (ref "P2") (pin "A6") (pinfunction "DP_A6") (pintype "passive"))
      (node (ref "P2") (pin "B6") (pinfunction "DP_B6") (pintype "passive"))
    )
    (net (code "53") (name "Net-(Q3A-S1)") (class "Default")
      (node (ref "Q3") (pin "1") (pinfunction "S1_1") (pintype "passive"))
      (node (ref "Q3") (pin "3") (pinfunction "S2_3") (pintype "passive"))
    )
    (net (code "54") (name "Net-(Q4A-S1)") (class "Default")
      (node (ref "Q4") (pin "1") (pinfunction "S1_1") (pintype "passive"))
      (node (ref "Q4") (pin "3") (pinfunction "S2_3") (pintype "passive"))
    )
    (net (code "55") (name "Net-(Q5A-S1)") (class "Default")
      (node (ref "Q5") (pin "1") (pinfunction "S1_1") (pintype "passive"))
      (node (ref "Q5") (pin "3") (pinfunction "S2_3") (pintype "passive"))
    )
    (net (code "56") (name "Net-(Q6A-S1)") (class "Default")
      (node (ref "Q6") (pin "1") (pinfunction "S1_1") (pintype "passive"))
      (node (ref "Q6") (pin "3") (pinfunction "S2_3") (pintype "passive"))
    )
    (net (code "57") (name "Net-(R21-Pad2)") (class "Default")
      (node (ref "R21") (pin "2") (pinfunction "2_2") (pintype "passive"))
      (node (ref "S1") (pin "1") (pinfunction "1_1") (pintype "passive"))
    )
    (net (code "58") (name "Net-(R22-Pad2)") (class "Default")
      (node (ref "R22") (pin "2") (pinfunction "2_2") (pintype "passive"))
      (node (ref "S1") (pin "2") (pinfunction "2_2") (pintype "passive"))
    )
    (net (code "59") (name "Net-(R23-Pad2)") (class "Default")
      (node (ref "R23") (pin "2") (pinfunction "2_2") (pintype "passive"))
      (node (ref "S1") (pin "3") (pinfunction "3_3") (pintype "passive"))
    )
    (net (code "60") (name "Net-(R24-Pad2)") (class "Default")
      (node (ref "R24") (pin "2") (pinfunction "2_2") (pintype "passive"))
      (node (ref "S1") (pin "4") (pinfunction "4_4") (pintype "passive"))
    )
    (net (code "61") (name "Net-(U1-BIAS)") (class "Default")
      (node (ref "C1") (pin "1") (pinfunction "1_1") (pintype "passive"))
      (node (ref "R1") (pin "1") (pinfunction "1_1") (pintype "passive"))
      (node (ref "U1") (pin "1") (pinfunction "BIAS_1") (pintype "passive"))
    )
    (net (code "62") (name "Net-(U1-CBST)") (class "Default")
      (node (ref "C13") (pin "1") (pinfunction "1_1") (pintype "passive"))
      (node (ref "R4") (pin "1") (pinfunction "1_1") (pintype "passive"))
      (node (ref "U1") (pin "14") (pinfunction "CBST_14") (pintype "passive"))
    )
    (net (code "63") (name "Net-(U1-FREQ)") (class "Default")
      (node (ref "R6") (pin "1") (pinfunction "1_1") (pintype "passive"))
      (node (ref "U1") (pin "6") (pinfunction "FREQ_6") (pintype "passive"))
    )
    (net (code "64") (name "Net-(U1-RBST)") (class "Default")
      (node (ref "R4") (pin "2") (pinfunction "2_2") (pintype "passive"))
      (node (ref "U1") (pin "13") (pinfunction "RBST_13") (pintype "passive"))
    )
    (net (code "65") (name "Net-(U1-SW)") (class "Default")
      (node (ref "C13") (pin "2") (pinfunction "2_2") (pintype "passive"))
      (node (ref "L1") (pin "1") (pinfunction "1_1") (pintype "passive"))
      (node (ref "U1") (pin "10") (pinfunction "SW_10") (pintype "passive"))
    )
    (net (code "66") (name "Net-(U1-VCC)") (class "Default")
      (node (ref "C14") (pin "1") (pinfunction "1_1") (pintype "passive"))
      (node (ref "U1") (pin "2") (pinfunction "VCC_2") (pintype "passive"))
    )
    (net (code "67") (name "Net-(U2-IO1)") (class "Default")
      (node (ref "Q3") (pin "7") (pinfunction "D1_7") (pintype "passive"))
      (node (ref "Q3") (pin "8") (pinfunction "D1_8") (pintype "passive"))
      (node (ref "R13") (pin "2") (pinfunction "2_2") (pintype "passive"))
      (node (ref "U2") (pin "1") (pinfunction "IO1_1") (pintype "bidirectional"))
    )
    (net (code "68") (name "Net-(U2-IO4)") (class "Default")
      (node (ref "Q4") (pin "7") (pinfunction "D1_7") (pintype "passive"))
      (node (ref "Q4") (pin "8") (pinfunction "D1_8") (pintype "passive"))
      (node (ref "R12") (pin "2") (pinfunction "2_2") (pintype "passive"))
      (node (ref "U2") (pin "6") (pinfunction "IO4_6") (pintype "bidirectional"))
    )
    (net (code "69") (name "Net-(U3-CAP2)") (class "Default")
      (node (ref "C23") (pin "2") (pinfunction "2_2") (pintype "passive"))
      (node (ref "U3") (pin "42") (pinfunction "CAP2_42") (pintype "power_in"))
    )
    (net (code "70") (name "Net-(U3-PB12{slash}LO2CAP2)") (class "Default")
      (node (ref "C23") (pin "1") (pinfunction "1_1") (pintype "passive"))
      (node (ref "U3") (pin "41") (pinfunction "PB12/LO2CAP2_41") (pintype "bidirectional"))
    )
    (net (code "71") (name "VHV") (class "Default")
      (node (ref "C15") (pin "2") (pinfunction "2_2") (pintype "passive"))
      (node (ref "C19") (pin "1") (pinfunction "1_1") (pintype "passive"))
      (node (ref "Q1") (pin "5") (pinfunction "D_5") (pintype "passive"))
      (node (ref "Q1") (pin "6") (pinfunction "6_6") (pintype "passive"))
      (node (ref "Q1") (pin "7") (pinfunction "7_7") (pintype "passive"))
      (node (ref "Q1") (pin "8") (pinfunction "8_8") (pintype "passive"))
      (node (ref "Q2") (pin "5") (pinfunction "D_5") (pintype "passive"))
      (node (ref "Q2") (pin "6") (pinfunction "6_6") (pintype "passive"))
      (node (ref "Q2") (pin "7") (pinfunction "7_7") (pintype "passive"))
      (node (ref "Q2") (pin "8") (pinfunction "8_8") (pintype "passive"))
      (node (ref "Q3") (pin "5") (pinfunction "D2_5") (pintype "passive"))
      (node (ref "Q3") (pin "6") (pinfunction "D2_6") (pintype "passive"))
      (node (ref "Q4") (pin "5") (pinfunction "D2_5") (pintype "passive"))
      (node (ref "Q4") (pin "6") (pinfunction "D2_6") (pintype "passive"))
      (node (ref "U3") (pin "9") (pinfunction "VHV_9") (pintype "power_in"))
    )
    (net (code "72") (name "unconnected-(U1-PG-Pad5)") (class "Default")
      (node (ref "U1") (pin "5") (pinfunction "PG_5") (pintype "passive"))
    )
    (net (code "73") (name "unconnected-(U3-GND-Pad0)") (class "Default")
      (node (ref "U3") (pin "0") (pinfunction "GND_0") (pintype "power_in"))
    )
    (net (code "74") (name "unconnected-(U3-ISP1-Pad25)") (class "Default")
      (node (ref "U3") (pin "25") (pinfunction "ISP1_25") (pintype "input+no_connect"))
    )
    (net (code "75") (name "unconnected-(U3-PB7{slash}HVOD-Pad48)") (class "Default")
      (node (ref "U3") (pin "48") (pinfunction "PB7/HVOD_48") (pintype "open_collector+no_connect"))
    )
  )
)
